# ultrasonic_imu_sensor.net
KiCad netlist of a schematic drawn in Altium Designer
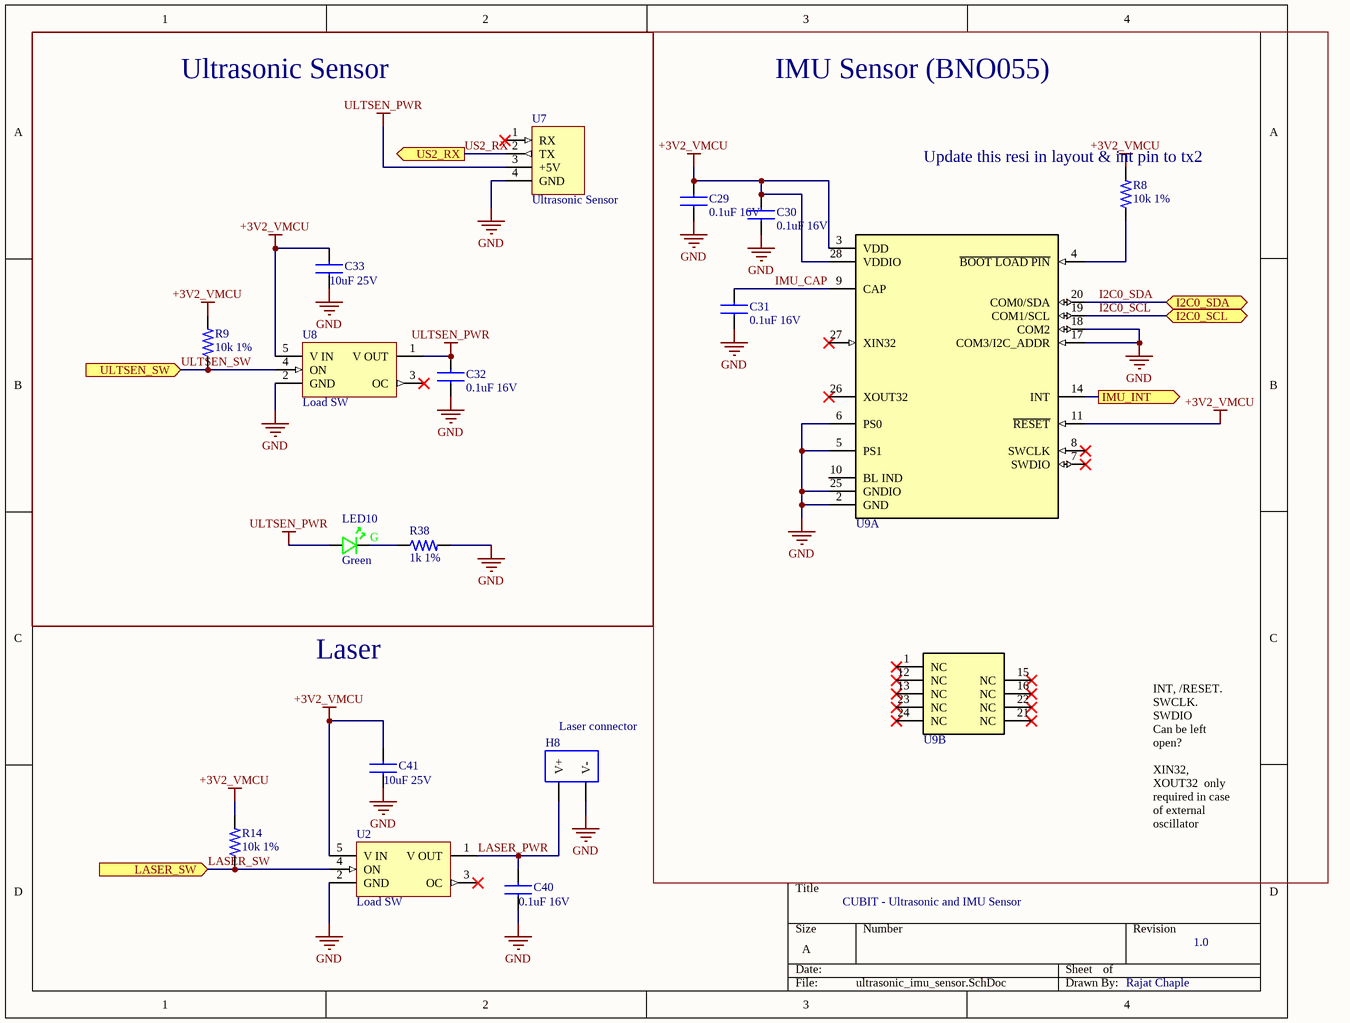
[diagram p0: ultrasonic_imu_sensor.SchDoc]

(export (version "E")
  (design (tool "Eeschema 10.0.6"))
  (components
    (comp (ref "C29")
      (value "0.1uF 16V")
      (footprint "CAP_0603_1MM")
      (description "Cap Ceramic 0.1uF 16V X7R 10% SMD 0603 125°C Paper T/R")
      (fields
        (field (name "MANUFACTURER") "KEMET")
        (field (name "MANUFACTURER PART NUMBER") "C0805C104K4RACAUTO")
      )
      (libsource (lib "LPEDT_proj_lib") (part "C0805C104K4RACAUTO"))
    )
    (comp (ref "C30")
      (value "0.1uF 16V")
      (footprint "CAP_0603_1MM")
      (description "Cap Ceramic 0.1uF 16V X7R 10% SMD 0603 125°C Paper T/R")
      (fields
        (field (name "MANUFACTURER") "KEMET")
        (field (name "MANUFACTURER PART NUMBER") "C0805C104K4RACAUTO")
      )
      (libsource (lib "LPEDT_proj_lib") (part "C0805C104K4RACAUTO"))
    )
    (comp (ref "C31")
      (value "0.1uF 16V")
      (footprint "CAP_0603_1MM")
      (description "Cap Ceramic 0.1uF 16V X7R 10% SMD 0603 125°C Paper T/R")
      (fields
        (field (name "MANUFACTURER") "KEMET")
        (field (name "MANUFACTURER PART NUMBER") "C0805C104K4RACAUTO")
      )
      (libsource (lib "LPEDT_proj_lib") (part "C0805C104K4RACAUTO"))
    )
    (comp (ref "C32")
      (value "0.1uF 16V")
      (footprint "CAP_0603_1MM")
      (description "Cap Ceramic 0.1uF 16V X7R 10% SMD 0603 125°C Paper T/R")
      (fields
        (field (name "MANUFACTURER") "KEMET")
        (field (name "MANUFACTURER PART NUMBER") "C0805C104K4RACAUTO")
      )
      (libsource (lib "LPEDT_proj_lib") (part "C0805C104K4RACAUTO"))
    )
    (comp (ref "C33")
      (value "10uF 25V")
      (footprint "CAP_0805_02X125")
      (description "Cap 0805 25 V 10 uF ±20% Tolerance X5R Monolithic Ceramic Chip Capacitor")
      (fields
        (field (name "MANUFACTURER") "Murata")
        (field (name "MANUFACTURER PART NUMBER") "GRM21BR61E106KA73K")
      )
      (libsource (lib "LPEDT_proj_lib") (part "GRM21BR61E106KA73K"))
    )
    (comp (ref "C40")
      (value "0.1uF 16V")
      (footprint "CAP_0603_1MM")
      (description "Cap Ceramic 0.1uF 16V X7R 10% SMD 0603 125°C Paper T/R")
      (fields
        (field (name "MANUFACTURER") "KEMET")
        (field (name "MANUFACTURER PART NUMBER") "C0805C104K4RACAUTO")
      )
      (libsource (lib "LPEDT_proj_lib") (part "C0805C104K4RACAUTO"))
    )
    (comp (ref "C41")
      (value "10uF 25V")
      (footprint "CAP_0805_02X125")
      (description "Cap 0805 25 V 10 uF ±20% Tolerance X5R Monolithic Ceramic Chip Capacitor")
      (fields
        (field (name "MANUFACTURER") "Murata")
        (field (name "MANUFACTURER PART NUMBER") "GRM21BR61E106KA73K")
      )
      (libsource (lib "LPEDT_proj_lib") (part "GRM21BR61E106KA73K"))
    )
    (comp (ref "H8")
      (value "Laser connector")
      (footprint "BAT_CONN")
      (description "2.00mm Pitch")
      (libsource (lib "LPEDT_proj_lib") (part "batt_conn_pad"))
    )
    (comp (ref "LED10")
      (value "Green")
      (footprint "LED_0603_RED_WL-SMCW")
      (description "Led Green Clear 0603 SMD")
      (fields
        (field (name "MANUFACTURER") "QT-Brightek")
        (field (name "MANUFACTURER PART NUMBER") "QBLP601-AG1")
      )
      (libsource (lib "LPEDT_proj_lib") (part "QBLP601-AG1"))
    )
    (comp (ref "R8")
      (value "10k 1%")
      (footprint "2_Chip_0603_RMCF")
      (description "Res 10K Ohm 1% 1/10W ±100ppm/°C Molded SMD SMD Paper T/R")
      (fields
        (field (name "MANUFACTURER") "Stackpole Electronics")
        (field (name "MANUFACTURER PART NUMBER") "RMCF0603FT10K0")
      )
      (libsource (lib "LPEDT_proj_lib") (part "RMCF0603FT10K0"))
    )
    (comp (ref "R9")
      (value "10k 1%")
      (footprint "2_Chip_0603_RMCF")
      (description "Res 10K Ohm 1% 1/10W ±100ppm/°C Molded SMD SMD Paper T/R")
      (fields
        (field (name "MANUFACTURER") "Stackpole Electronics")
        (field (name "MANUFACTURER PART NUMBER") "RMCF0603FT10K0")
      )
      (libsource (lib "LPEDT_proj_lib") (part "RMCF0603FT10K0"))
    )
    (comp (ref "R14")
      (value "10k 1%")
      (footprint "2_Chip_0603_RMCF")
      (description "Res 10K Ohm 1% 1/10W ±100ppm/°C Molded SMD SMD Paper T/R")
      (fields
        (field (name "MANUFACTURER") "Stackpole Electronics")
        (field (name "MANUFACTURER PART NUMBER") "RMCF0603FT10K0")
      )
      (libsource (lib "LPEDT_proj_lib") (part "RMCF0603FT10K0"))
    )
    (comp (ref "R38")
      (value "1k 1%")
      (footprint "2_Chip_0603_RMCF")
      (description "Res 1K Ohm 1% 0.1W(1/10W) ±100ppm/C Pad SMD Automotive T/R")
      (fields
        (field (name "MANUFACTURER") "Stackpole Electronics")
        (field (name "MANUFACTURER PART NUMBER") "RMCF0603FT1K00")
      )
      (libsource (lib "LPEDT_proj_lib") (part "RMCF0603FT1K00"))
    )
    (comp (ref "U2")
      (value "Load SW")
      (footprint "SOT65P210X110-5N")
      (description "5.5-V, 0.1-A, 500-mΩ, load switch with current limit and active low enable 5-SC70 -40 to 85")
      (fields
        (field (name "MANUFACTURER") "Texas Instruments")
        (field (name "MANUFACTURER PART NUMBER") "TPS22942DCKR")
      )
      (libsource (lib "LPEDT_proj_lib") (part "TPS22942DCKR"))
    )
    (comp (ref "U7")
      (value "Ultrasonic Sensor")
      (footprint "4_PIN_ultrasonic_sensor")
      (libsource (lib "LPEDT_proj_lib") (part "Ultrasonic Sensor"))
    )
    (comp (ref "U8")
      (value "Load SW")
      (footprint "SOT65P210X110-5N")
      (description "5.5-V, 0.1-A, 500-mΩ, load switch with current limit and active low enable 5-SC70 -40 to 85")
      (fields
        (field (name "MANUFACTURER") "Texas Instruments")
        (field (name "MANUFACTURER PART NUMBER") "TPS22942DCKR")
      )
      (libsource (lib "LPEDT_proj_lib") (part "TPS22942DCKR"))
    )
    (comp (ref "U9")
      (value "BNO005")
      (footprint "LGA28R50P4X10_380X520X100")
      (libsource (lib "LPEDT_proj_lib") (part "BNO055"))
    )
  )
  (nets
    (net (code "1") (name "+3V2_VMCU") (class "Default")
      (node (ref "C29") (pin "1") (pinfunction "1_1") (pintype "passive"))
      (node (ref "C30") (pin "1") (pinfunction "1_1") (pintype "passive"))
      (node (ref "C33") (pin "1") (pinfunction "1_1") (pintype "passive"))
      (node (ref "C41") (pin "1") (pinfunction "1_1") (pintype "passive"))
      (node (ref "R14") (pin "2") (pinfunction "2_2") (pintype "passive"))
      (node (ref "R8") (pin "2") (pinfunction "2_2") (pintype "passive"))
      (node (ref "R9") (pin "2") (pinfunction "2_2") (pintype "passive"))
      (node (ref "U2") (pin "5") (pinfunction "V_IN_5") (pintype "power_in"))
      (node (ref "U8") (pin "5") (pinfunction "V_IN_5") (pintype "power_in"))
      (node (ref "U9") (pin "11") (pinfunction "~{RESET}_11") (pintype "input"))
      (node (ref "U9") (pin "28") (pinfunction "VDDIO_28") (pintype "power_in"))
      (node (ref "U9") (pin "3") (pinfunction "VDD_3") (pintype "power_in"))
    )
    (net (code "2") (name "/I2C0_SCL") (class "Default")
      (node (ref "U9") (pin "19") (pinfunction "COM1/SCL_19") (pintype "bidirectional"))
    )
    (net (code "3") (name "/I2C0_SDA") (class "Default")
      (node (ref "U9") (pin "20") (pinfunction "COM0/SDA_20") (pintype "bidirectional"))
    )
    (net (code "4") (name "/IMU_CAP") (class "Default")
      (node (ref "C31") (pin "1") (pinfunction "1_1") (pintype "passive"))
      (node (ref "U9") (pin "9") (pinfunction "CAP_9") (pintype "passive"))
    )
    (net (code "5") (name "/IMU_INT") (class "Default")
      (node (ref "U9") (pin "14") (pinfunction "INT_14") (pintype "passive"))
    )
    (net (code "6") (name "/LASER_PWR") (class "Default")
      (node (ref "C40") (pin "1") (pinfunction "1_1") (pintype "passive"))
      (node (ref "H8") (pin "V+") (pinfunction "V+_V+") (pintype "passive"))
      (node (ref "U2") (pin "1") (pinfunction "V_OUT_1") (pintype "power_in"))
    )
    (net (code "7") (name "/LASER_SW") (class "Default")
      (node (ref "R14") (pin "1") (pinfunction "1_1") (pintype "passive"))
      (node (ref "U2") (pin "4") (pinfunction "ON_4") (pintype "input"))
    )
    (net (code "8") (name "/ULTSEN_SW") (class "Default")
      (node (ref "R9") (pin "1") (pinfunction "1_1") (pintype "passive"))
      (node (ref "U8") (pin "4") (pinfunction "ON_4") (pintype "input"))
    )
    (net (code "9") (name "/US2_RX") (class "Default")
      (node (ref "U7") (pin "2") (pinfunction "TX_2") (pintype "output"))
    )
    (net (code "10") (name "GND") (class "Default")
      (node (ref "C29") (pin "2") (pinfunction "2_2") (pintype "passive"))
      (node (ref "C30") (pin "2") (pinfunction "2_2") (pintype "passive"))
      (node (ref "C31") (pin "2") (pinfunction "2_2") (pintype "passive"))
      (node (ref "C32") (pin "2") (pinfunction "2_2") (pintype "passive"))
      (node (ref "C33") (pin "2") (pinfunction "2_2") (pintype "passive"))
      (node (ref "C40") (pin "2") (pinfunction "2_2") (pintype "passive"))
      (node (ref "C41") (pin "2") (pinfunction "2_2") (pintype "passive"))
      (node (ref "H8") (pin "V-") (pinfunction "V-_V-") (pintype "passive"))
      (node (ref "R38") (pin "2") (pinfunction "2_2") (pintype "passive"))
      (node (ref "U2") (pin "2") (pinfunction "GND_2") (pintype "power_in"))
      (node (ref "U7") (pin "4") (pinfunction "GND_4") (pintype "power_in"))
      (node (ref "U8") (pin "2") (pinfunction "GND_2") (pintype "power_in"))
      (node (ref "U9") (pin "17") (pinfunction "COM3/I2C_ADDR_17") (pintype "input"))
      (node (ref "U9") (pin "18") (pinfunction "COM2_18") (pintype "bidirectional"))
      (node (ref "U9") (pin "2") (pinfunction "GND_2") (pintype "power_in"))
      (node (ref "U9") (pin "25") (pinfunction "GNDIO_25") (pintype "power_in"))
      (node (ref "U9") (pin "5") (pinfunction "PS1_5") (pintype "power_in"))
      (node (ref "U9") (pin "6") (pinfunction "PS0_6") (pintype "power_in"))
    )
    (net (code "11") (name "Net-(LED10-PadC)") (class "Default")
      (node (ref "LED10") (pin "C") (pinfunction "C_C") (pintype "passive"))
      (node (ref "R38") (pin "1") (pinfunction "1_1") (pintype "passive"))
    )
    (net (code "12") (name "Net-(U9A-~{BOOT_LOAD_PIN})") (class "Default")
      (node (ref "R8") (pin "1") (pinfunction "1_1") (pintype "passive"))
      (node (ref "U9") (pin "4") (pinfunction "~{BOOT_LOAD_PIN}_4") (pintype "input"))
    )
    (net (code "13") (name "ULTSEN_PWR") (class "Default")
      (node (ref "C32") (pin "1") (pinfunction "1_1") (pintype "passive"))
      (node (ref "LED10") (pin "A") (pinfunction "A_A") (pintype "passive"))
      (node (ref "U7") (pin "3") (pinfunction "+5V_3") (pintype "power_in"))
      (node (ref "U8") (pin "1") (pinfunction "V_OUT_1") (pintype "power_in"))
    )
    (net (code "14") (name "unconnected-(U2-OC-Pad3)") (class "Default")
      (node (ref "U2") (pin "3") (pinfunction "OC_3") (pintype "output+no_connect"))
    )
    (net (code "15") (name "unconnected-(U7-RX-Pad1)") (class "Default")
      (node (ref "U7") (pin "1") (pinfunction "RX_1") (pintype "input+no_connect"))
    )
    (net (code "16") (name "unconnected-(U8-OC-Pad3)") (class "Default")
      (node (ref "U8") (pin "3") (pinfunction "OC_3") (pintype "output+no_connect"))
    )
    (net (code "17") (name "unconnected-(U9A-BL_IND-Pad10)") (class "Default")
      (node (ref "U9") (pin "10") (pinfunction "BL_IND_10") (pintype "power_in"))
    )
    (net (code "18") (name "unconnected-(U9A-SWCLK-Pad8)") (class "Default")
      (node (ref "U9") (pin "8") (pinfunction "SWCLK_8") (pintype "input+no_connect"))
    )
    (net (code "19") (name "unconnected-(U9A-SWDIO-Pad7)") (class "Default")
      (node (ref "U9") (pin "7") (pinfunction "SWDIO_7") (pintype "bidirectional+no_connect"))
    )
    (net (code "20") (name "unconnected-(U9A-XIN32-Pad27)") (class "Default")
      (node (ref "U9") (pin "27") (pinfunction "XIN32_27") (pintype "input+no_connect"))
    )
    (net (code "21") (name "unconnected-(U9A-XOUT32-Pad26)") (class "Default")
      (node (ref "U9") (pin "26") (pinfunction "XOUT32_26") (pintype "passive+no_connect"))
    )
    (net (code "22") (name "unconnected-(U9B-NC-Pad1)") (class "Default")
      (node (ref "U9") (pin "1") (pinfunction "NC_1") (pintype "passive+no_connect"))
    )
    (net (code "23") (name "unconnected-(U9B-NC-Pad12)") (class "Default")
      (node (ref "U9") (pin "12") (pinfunction "NC_12") (pintype "passive+no_connect"))
    )
    (net (code "24") (name "unconnected-(U9B-NC-Pad13)") (class "Default")
      (node (ref "U9") (pin "13") (pinfunction "NC_13") (pintype "passive+no_connect"))
    )
    (net (code "25") (name "unconnected-(U9B-NC-Pad15)") (class "Default")
      (node (ref "U9") (pin "15") (pinfunction "NC_15") (pintype "passive+no_connect"))
    )
    (net (code "26") (name "unconnected-(U9B-NC-Pad16)") (class "Default")
      (node (ref "U9") (pin "16") (pinfunction "NC_16") (pintype "passive+no_connect"))
    )
    (net (code "27") (name "unconnected-(U9B-NC-Pad21)") (class "Default")
      (node (ref "U9") (pin "21") (pinfunction "NC_21") (pintype "passive+no_connect"))
    )
    (net (code "28") (name "unconnected-(U9B-NC-Pad22)") (class "Default")
      (node (ref "U9") (pin "22") (pinfunction "NC_22") (pintype "passive+no_connect"))
    )
    (net (code "29") (name "unconnected-(U9B-NC-Pad23)") (class "Default")
      (node (ref "U9") (pin "23") (pinfunction "NC_23") (pintype "passive+no_connect"))
    )
    (net (code "30") (name "unconnected-(U9B-NC-Pad24)") (class "Default")
      (node (ref "U9") (pin "24") (pinfunction "NC_24") (pintype "passive+no_connect"))
    )
  )
)
